# TinyGame_RC1_JTAG.net
KiCad netlist of a schematic drawn in EAGLE
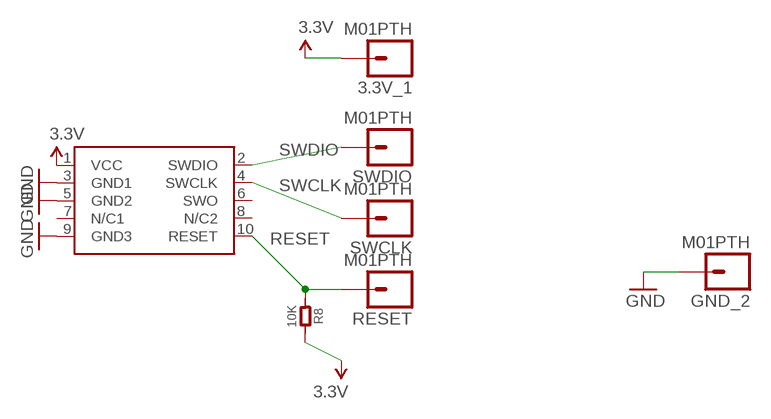
[diagram p0: schematic, sheet 1]

(export (version "E")
  (design (tool "Eeschema 10.0.6"))
  (components
    (comp (ref "3.3V_1")
      (value "M01PTH")
      (footprint "eagle-import:1X01")
      (libsource (lib "eagle-import") (part "M01PTH"))
    )
    (comp (ref "GND_2")
      (value "M01PTH")
      (footprint "eagle-import:1X01")
      (libsource (lib "eagle-import") (part "M01PTH"))
    )
    (comp (ref "R8")
      (value "10K")
      (footprint "eagle-import:R0603")
      (libsource (lib "eagle-import") (part "R-0603"))
    )
    (comp (ref "RESET")
      (value "M01PTH")
      (footprint "eagle-import:1X01")
      (libsource (lib "eagle-import") (part "M01PTH"))
    )
    (comp (ref "SWCLK")
      (value "M01PTH")
      (footprint "eagle-import:1X01")
      (libsource (lib "eagle-import") (part "M01PTH"))
    )
    (comp (ref "SWD1")
      (value "CORTEX_SWDVERT")
      (footprint "eagle-import:SWD_VERTICAL")
      (libsource (lib "eagle-import") (part "CORTEX_SWDVERT"))
    )
    (comp (ref "SWDIO")
      (value "M01PTH")
      (footprint "eagle-import:1X01")
      (libsource (lib "eagle-import") (part "M01PTH"))
    )
  )
  (nets
    (net (code "1") (name "/RESET") (class "Default")
      (node (ref "R8") (pin "1") (pinfunction "1_1") (pintype "bidirectional"))
      (node (ref "RESET") (pin "1") (pinfunction "1_1") (pintype "passive"))
      (node (ref "SWD1") (pin "10") (pinfunction "RESET_10") (pintype "bidirectional"))
    )
    (net (code "2") (name "/SWCLK") (class "Default")
      (node (ref "SWCLK") (pin "1") (pinfunction "1_1") (pintype "passive"))
      (node (ref "SWD1") (pin "4") (pinfunction "SWCLK_4") (pintype "bidirectional"))
    )
    (net (code "3") (name "/SWDIO") (class "Default")
      (node (ref "SWD1") (pin "2") (pinfunction "SWDIO_2") (pintype "bidirectional"))
      (node (ref "SWDIO") (pin "1") (pinfunction "1_1") (pintype "passive"))
    )
    (net (code "4") (name "3.3V") (class "Default")
      (node (ref "3.3V_1") (pin "1") (pinfunction "1_1") (pintype "passive"))
      (node (ref "R8") (pin "2") (pinfunction "2_2") (pintype "bidirectional"))
      (node (ref "SWD1") (pin "1") (pinfunction "VCC_1") (pintype "bidirectional"))
    )
    (net (code "5") (name "GND") (class "Default")
      (node (ref "GND_2") (pin "1") (pinfunction "1_1") (pintype "passive"))
      (node (ref "SWD1") (pin "3") (pinfunction "GND1_3") (pintype "bidirectional"))
      (node (ref "SWD1") (pin "5") (pinfunction "GND2_5") (pintype "bidirectional"))
      (node (ref "SWD1") (pin "9") (pinfunction "GND3_9") (pintype "bidirectional"))
    )
    (net (code "6") (name "unconnected-(SWD1-N{slash}C1-Pad7)") (class "Default")
      (node (ref "SWD1") (pin "7") (pinfunction "N/C1_7") (pintype "bidirectional"))
    )
    (net (code "7") (name "unconnected-(SWD1-N{slash}C2-Pad8)") (class "Default")
      (node (ref "SWD1") (pin "8") (pinfunction "N/C2_8") (pintype "bidirectional"))
    )
    (net (code "8") (name "unconnected-(SWD1-SWO-Pad6)") (class "Default")
      (node (ref "SWD1") (pin "6") (pinfunction "SWO_6") (pintype "bidirectional"))
    )
  )
)
